# FDC.net
KiCad netlist of a schematic drawn in Altium Designer
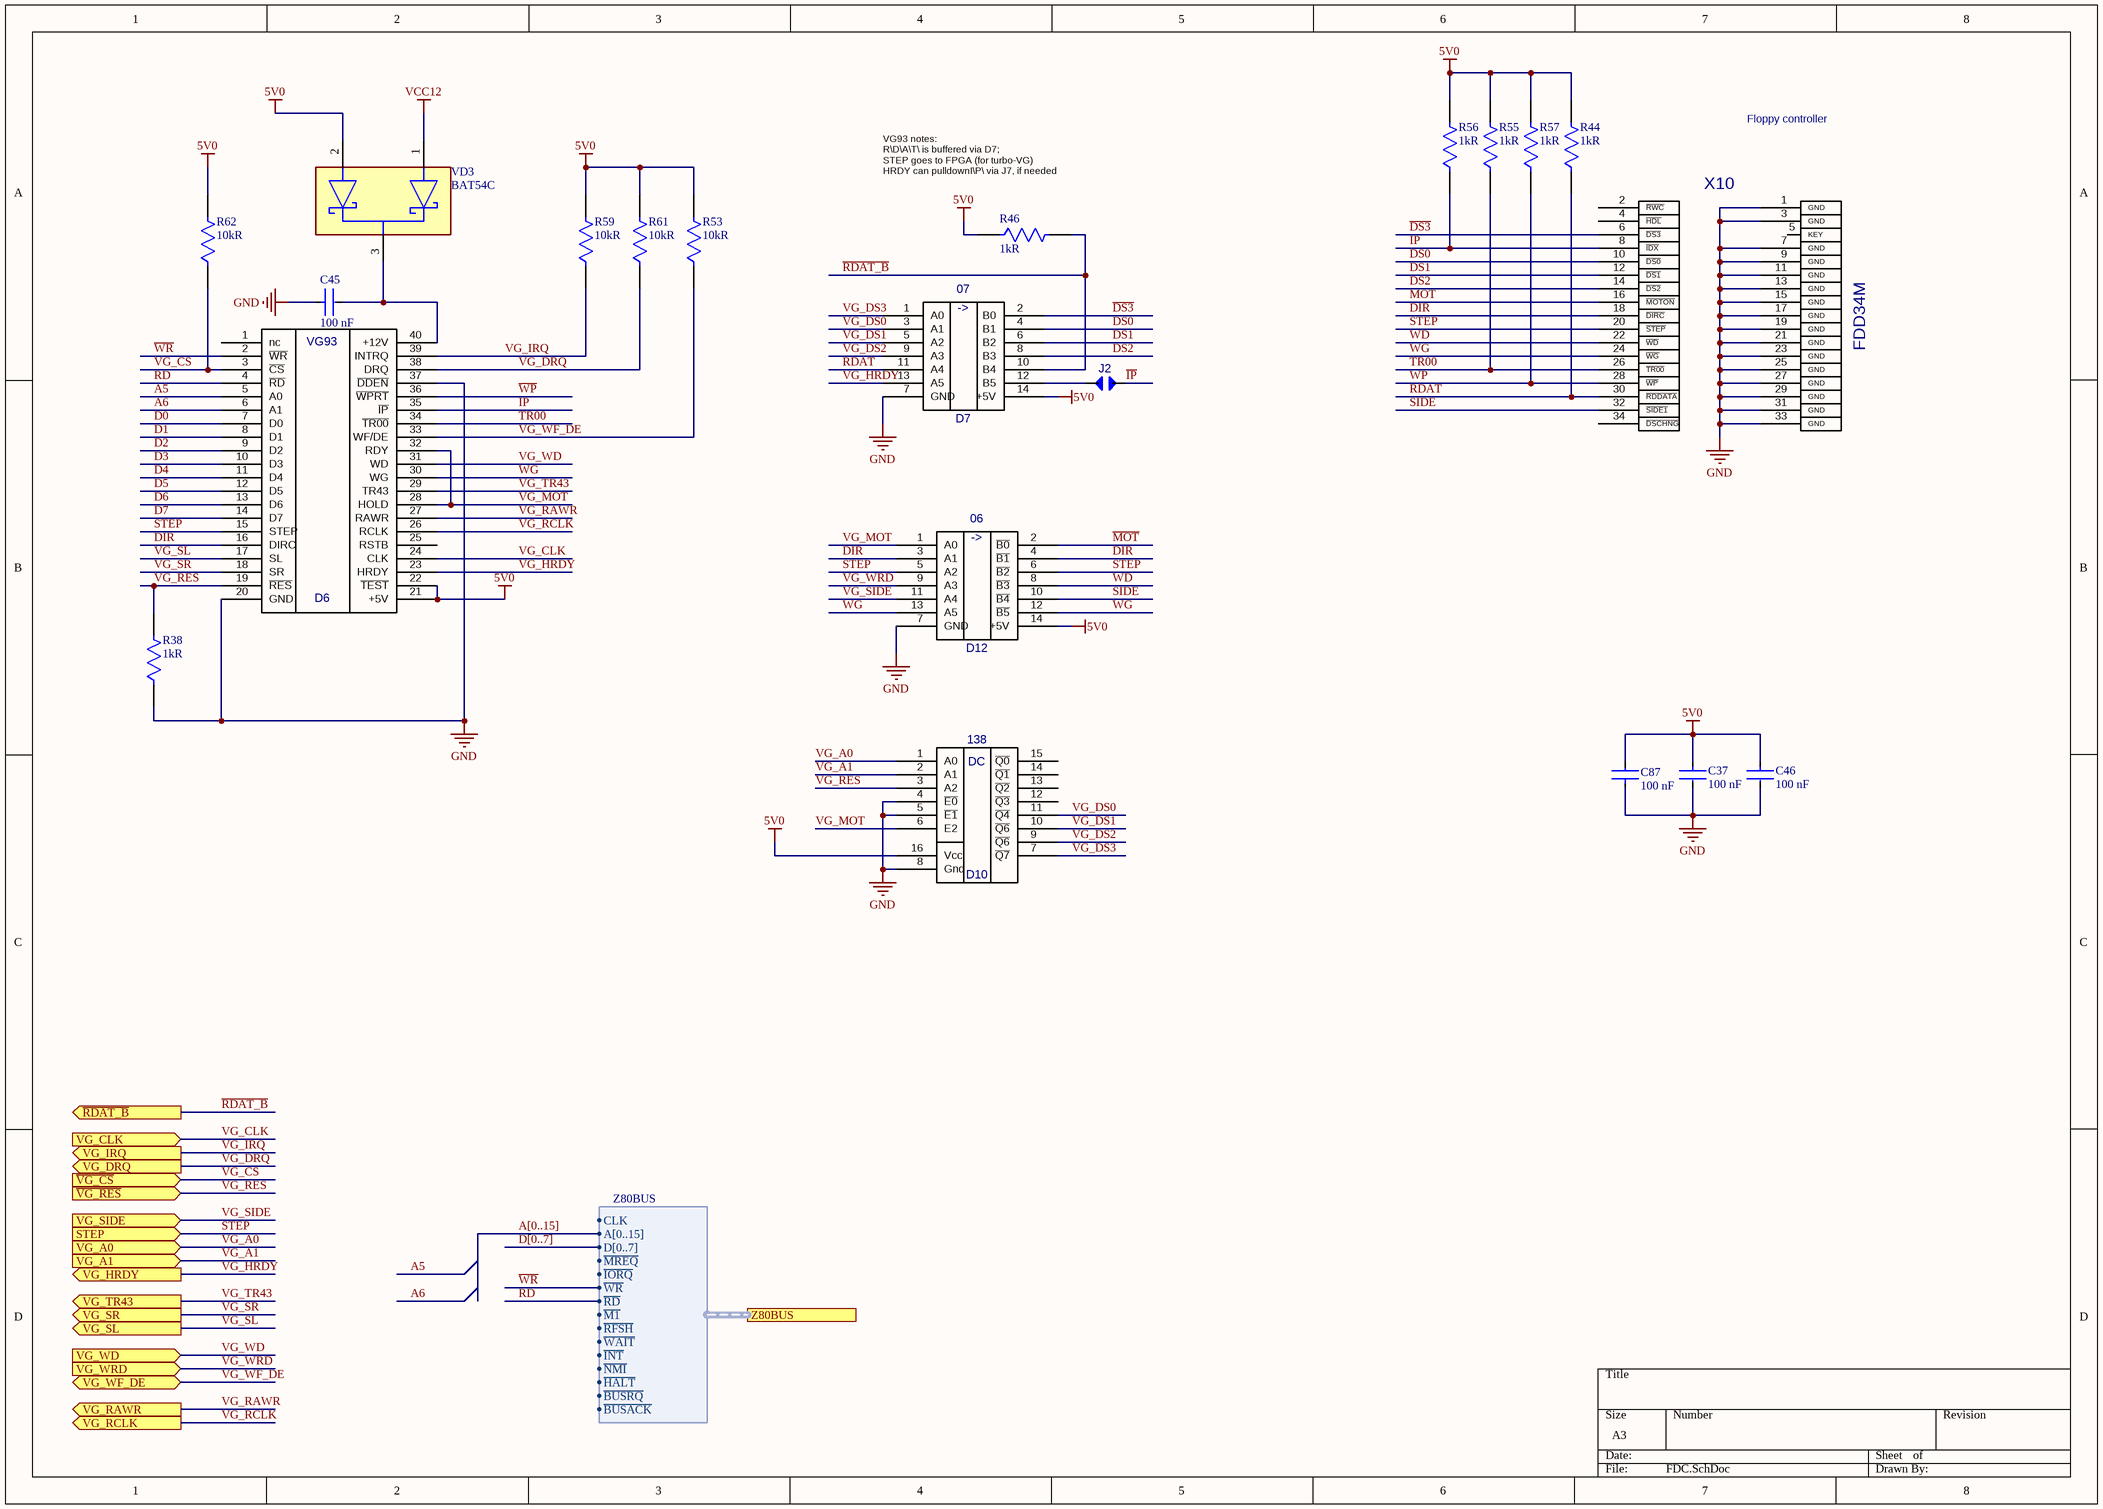
[diagram p0: FDC.SchDoc]

(export (version "E")
  (design (tool "Eeschema 10.0.6"))
  (components
    (comp (ref "C37")
      (value "CC0805KRX7R9BB104")
      (footprint "FP-CC0805-0_85-IPC_A")
      (description "CAP CER 0.1UF 50V X7R 0805")
      (fields (field (name "CAPACITANCE") "100 nF") (field (name "MANUFACTURER") "Yageo"))
      (libsource (lib "SchLib") (part "CMP-2100-03606-3"))
    )
    (comp (ref "C45")
      (value "CC0805KRX7R9BB104")
      (footprint "FP-CC0805-0_85-IPC_A")
      (description "CAP CER 0.1UF 50V X7R 0805")
      (fields (field (name "CAPACITANCE") "100 nF") (field (name "MANUFACTURER") "Yageo"))
      (libsource (lib "SchLib") (part "CMP-2100-03606-3"))
    )
    (comp (ref "C46")
      (value "CC0805KRX7R9BB104")
      (footprint "FP-CC0805-0_85-IPC_A")
      (description "CAP CER 0.1UF 50V X7R 0805")
      (fields (field (name "CAPACITANCE") "100 nF") (field (name "MANUFACTURER") "Yageo"))
      (libsource (lib "SchLib") (part "CMP-2100-03606-3"))
    )
    (comp (ref "C87")
      (value "CC0805KRX7R9BB104")
      (footprint "FP-CC0805-0_85-IPC_A")
      (description "CAP CER 0.1UF 50V X7R 0805")
      (fields (field (name "CAPACITANCE") "100 nF") (field (name "MANUFACTURER") "Yageo"))
      (libsource (lib "SchLib") (part "CMP-2100-03606-3"))
    )
    (comp (ref "D6") (value "KR1818VG93") (footprint "DIP40") (libsource (lib "SchLib") (part "KR1818VG93")))
    (comp (ref "D7") (value "07") (footprint "SO14") (libsource (lib "SchLib") (part "07")))
    (comp (ref "D10") (value "138") (footprint "SO16") (libsource (lib "SchLib") (part "138")))
    (comp (ref "D12") (value "06") (footprint "SO14") (libsource (lib "SchLib") (part "06")))
    (comp (ref "J2")
      (value "JUMPER")
      (footprint "JUMPER_JUMPER(Primary)")
      (description "HLT->~IP")
      (libsource (lib "SchLib") (part "JUMPER"))
    )
    (comp (ref "R38")
      (value "CRCW08051K00FKEAHP")
      (footprint "FP-CRCW0805-HPe3-IPC_A")
      (description "RES Thick Film, 1kΩ, 1%, 0.5W, 100ppm/°C, 0805")
      (fields (field (name "RESISTANCE") "1kR") (field (name "MANUFACTURER") "Vishay Dale"))
      (libsource (lib "SchLib") (part "CMP-02407-004529-1"))
    )
    (comp (ref "R44")
      (value "CRCW08051K00FKEAHP")
      (footprint "FP-CRCW0805-HPe3-IPC_A")
      (description "RES Thick Film, 1kΩ, 1%, 0.5W, 100ppm/°C, 0805")
      (fields (field (name "RESISTANCE") "1kR") (field (name "MANUFACTURER") "Vishay Dale"))
      (libsource (lib "SchLib") (part "CMP-02407-004529-1"))
    )
    (comp (ref "R46")
      (value "CRCW08051K00FKEAHP")
      (footprint "FP-CRCW0805-HPe3-IPC_A")
      (description "RES Thick Film, 1kΩ, 1%, 0.5W, 100ppm/°C, 0805")
      (fields (field (name "RESISTANCE") "1kR") (field (name "MANUFACTURER") "Vishay Dale"))
      (libsource (lib "SchLib") (part "CMP-02407-004529-1"))
    )
    (comp (ref "R53")
      (value "CR0805-JW-103ELF")
      (footprint "FP-CR0805-IPC_A")
      (description "Thick Film Chip Resistors 0805 10kΩ 0.125W 5% 200ppm/°C")
      (fields (field (name "RESISTANCE") "10kR") (field (name "MANUFACTURER") "Bourns"))
      (libsource (lib "SchLib") (part "CMP-07231-003873-1"))
    )
    (comp (ref "R55")
      (value "CRCW08051K00FKEAHP")
      (footprint "FP-CRCW0805-HPe3-IPC_A")
      (description "RES Thick Film, 1kΩ, 1%, 0.5W, 100ppm/°C, 0805")
      (fields (field (name "RESISTANCE") "1kR") (field (name "MANUFACTURER") "Vishay Dale"))
      (libsource (lib "SchLib") (part "CMP-02407-004529-1"))
    )
    (comp (ref "R56")
      (value "CRCW08051K00FKEAHP")
      (footprint "FP-CRCW0805-HPe3-IPC_A")
      (description "RES Thick Film, 1kΩ, 1%, 0.5W, 100ppm/°C, 0805")
      (fields (field (name "RESISTANCE") "1kR") (field (name "MANUFACTURER") "Vishay Dale"))
      (libsource (lib "SchLib") (part "CMP-02407-004529-1"))
    )
    (comp (ref "R57")
      (value "CRCW08051K00FKEAHP")
      (footprint "FP-CRCW0805-HPe3-IPC_A")
      (description "RES Thick Film, 1kΩ, 1%, 0.5W, 100ppm/°C, 0805")
      (fields (field (name "RESISTANCE") "1kR") (field (name "MANUFACTURER") "Vishay Dale"))
      (libsource (lib "SchLib") (part "CMP-02407-004529-1"))
    )
    (comp (ref "R59")
      (value "CR0805-JW-103ELF")
      (footprint "FP-CR0805-IPC_A")
      (description "Thick Film Chip Resistors 0805 10kΩ 0.125W 5% 200ppm/°C")
      (fields (field (name "RESISTANCE") "10kR") (field (name "MANUFACTURER") "Bourns"))
      (libsource (lib "SchLib") (part "CMP-07231-003873-1"))
    )
    (comp (ref "R61")
      (value "CR0805-JW-103ELF")
      (footprint "FP-CR0805-IPC_A")
      (description "Thick Film Chip Resistors 0805 10kΩ 0.125W 5% 200ppm/°C")
      (fields (field (name "RESISTANCE") "10kR") (field (name "MANUFACTURER") "Bourns"))
      (libsource (lib "SchLib") (part "CMP-07231-003873-1"))
    )
    (comp (ref "R62")
      (value "CR0805-JW-103ELF")
      (footprint "FP-CR0805-IPC_A")
      (description "Thick Film Chip Resistors 0805 10kΩ 0.125W 5% 200ppm/°C")
      (fields (field (name "RESISTANCE") "10kR") (field (name "MANUFACTURER") "Bourns"))
      (libsource (lib "SchLib") (part "CMP-07231-003873-1"))
    )
    (comp (ref "VD3")
      (value "BAT54C")
      (footprint "FP-MA03D-MFG")
      (description "DIODE ARRAY SCHOTTKY 30V SOT23-3")
      (fields (field (name "MANUFACTURER") "ON Semiconductor / Fairchild"))
      (libsource (lib "SchLib") (part "CMP-07162-000010-1"))
    )
    (comp (ref "X10") (value "FDD34M") (footprint "FDD34M") (libsource (lib "SchLib") (part "FDD34M")))
  )
  (nets
    (net (code "16") (name "/A5") (class "Default")
      (node (ref "D6") (pin "5") (pinfunction "A0_5") (pintype "passive"))
    )
    (net (code "17") (name "/A6") (class "Default")
      (node (ref "D6") (pin "6") (pinfunction "A1_6") (pintype "passive"))
    )
    (net (code "19") (name "/D0") (class "Default")
      (node (ref "D6") (pin "7") (pinfunction "D0_7") (pintype "passive"))
    )
    (net (code "20") (name "/D1") (class "Default")
      (node (ref "D6") (pin "8") (pinfunction "D1_8") (pintype "passive"))
    )
    (net (code "21") (name "/D2") (class "Default")
      (node (ref "D6") (pin "9") (pinfunction "D2_9") (pintype "passive"))
    )
    (net (code "22") (name "/D3") (class "Default")
      (node (ref "D6") (pin "10") (pinfunction "D3_10") (pintype "passive"))
    )
    (net (code "23") (name "/D4") (class "Default")
      (node (ref "D6") (pin "11") (pinfunction "D4_11") (pintype "passive"))
    )
    (net (code "24") (name "/D5") (class "Default")
      (node (ref "D6") (pin "12") (pinfunction "D5_12") (pintype "passive"))
    )
    (net (code "25") (name "/D6") (class "Default")
      (node (ref "D6") (pin "13") (pinfunction "D6_13") (pintype "passive"))
    )
    (net (code "26") (name "/D7") (class "Default")
      (node (ref "D6") (pin "14") (pinfunction "D7_14") (pintype "passive"))
    )
    (net (code "27") (name "/DIR") (class "Default")
      (node (ref "D12") (pin "3") (pinfunction "A1_3") (pintype "passive"))
      (node (ref "D6") (pin "16") (pinfunction "DIRC_16") (pintype "passive"))
    )
    (net (code "29") (name "/STEP") (class "Default")
      (node (ref "D12") (pin "5") (pinfunction "A2_5") (pintype "passive"))
      (node (ref "D6") (pin "15") (pinfunction "STEP_15") (pintype "passive"))
    )
    (net (code "30") (name "/VG_A0") (class "Default")
      (node (ref "D10") (pin "1") (pinfunction "A0_1") (pintype "passive"))
    )
    (net (code "31") (name "/VG_A1") (class "Default")
      (node (ref "D10") (pin "2") (pinfunction "A1_2") (pintype "passive"))
    )
    (net (code "32") (name "/VG_CLK") (class "Default")
      (node (ref "D6") (pin "24") (pinfunction "CLK_24") (pintype "passive"))
    )
    (net (code "33") (name "/VG_DRQ") (class "Default")
      (node (ref "D6") (pin "38") (pinfunction "DRQ_38") (pintype "passive"))
      (node (ref "R61") (pin "1") (pinfunction "1_1") (pintype "passive"))
    )
    (net (code "34") (name "/VG_DS0") (class "Default")
      (node (ref "D10") (pin "11") (pinfunction "~{Q4}_11") (pintype "passive"))
      (node (ref "D7") (pin "3") (pinfunction "A1_3") (pintype "passive"))
    )
    (net (code "35") (name "/VG_DS1") (class "Default")
      (node (ref "D10") (pin "10") (pinfunction "~{Q6}_10") (pintype "passive"))
      (node (ref "D7") (pin "5") (pinfunction "A2_5") (pintype "passive"))
    )
    (net (code "36") (name "/VG_DS2") (class "Default")
      (node (ref "D10") (pin "9") (pinfunction "~{Q6}_9") (pintype "passive"))
      (node (ref "D7") (pin "9") (pinfunction "A3_9") (pintype "passive"))
    )
    (net (code "37") (name "/VG_DS3") (class "Default")
      (node (ref "D10") (pin "7") (pinfunction "~{Q7}_7") (pintype "passive"))
      (node (ref "D7") (pin "1") (pinfunction "A0_1") (pintype "passive"))
    )
    (net (code "38") (name "/VG_HRDY") (class "Default")
      (node (ref "D6") (pin "23") (pinfunction "HRDY_23") (pintype "passive"))
      (node (ref "D7") (pin "13") (pinfunction "A5_13") (pintype "passive"))
    )
    (net (code "39") (name "/VG_IRQ") (class "Default")
      (node (ref "D6") (pin "39") (pinfunction "INTRQ_39") (pintype "passive"))
      (node (ref "R59") (pin "1") (pinfunction "1_1") (pintype "passive"))
    )
    (net (code "40") (name "/VG_MOT") (class "Default")
      (node (ref "D10") (pin "6") (pinfunction "E2_6") (pintype "passive"))
      (node (ref "D12") (pin "1") (pinfunction "A0_1") (pintype "passive"))
      (node (ref "D6") (pin "28") (pinfunction "HOLD_28") (pintype "passive"))
      (node (ref "D6") (pin "32") (pinfunction "RDY_32") (pintype "passive"))
    )
    (net (code "41") (name "/VG_RAWR") (class "Default")
      (node (ref "D6") (pin "27") (pinfunction "RAWR_27") (pintype "passive"))
    )
    (net (code "42") (name "/VG_RCLK") (class "Default")
      (node (ref "D6") (pin "26") (pinfunction "RCLK_26") (pintype "passive"))
    )
    (net (code "43") (name "/VG_SIDE") (class "Default")
      (node (ref "D12") (pin "11") (pinfunction "A4_11") (pintype "passive"))
    )
    (net (code "44") (name "/VG_SL") (class "Default")
      (node (ref "D6") (pin "17") (pinfunction "SL_17") (pintype "passive"))
    )
    (net (code "45") (name "/VG_SR") (class "Default")
      (node (ref "D6") (pin "18") (pinfunction "SR_18") (pintype "passive"))
    )
    (net (code "46") (name "/VG_TR43") (class "Default")
      (node (ref "D6") (pin "29") (pinfunction "TR43_29") (pintype "passive"))
    )
    (net (code "47") (name "/VG_WD") (class "Default")
      (node (ref "D6") (pin "31") (pinfunction "WD_31") (pintype "passive"))
    )
    (net (code "48") (name "/VG_WF_DE") (class "Default")
      (node (ref "D6") (pin "33") (pinfunction "WF/DE_33") (pintype "passive"))
      (node (ref "R53") (pin "1") (pinfunction "1_1") (pintype "passive"))
    )
    (net (code "49") (name "/VG_WRD") (class "Default")
      (node (ref "D12") (pin "9") (pinfunction "A3_9") (pintype "passive"))
    )
    (net (code "50") (name "/WG") (class "Default")
      (node (ref "D12") (pin "13") (pinfunction "A5_13") (pintype "passive"))
      (node (ref "D6") (pin "30") (pinfunction "WG_30") (pintype "passive"))
    )
    (net (code "52") (name "/~{DIR}") (class "Default")
      (node (ref "D12") (pin "4") (pinfunction "~{B1}_4") (pintype "passive"))
      (node (ref "X10") (pin "18") (pinfunction "~{DIRC}_18") (pintype "passive"))
    )
    (net (code "53") (name "/~{DS0}") (class "Default")
      (node (ref "D7") (pin "4") (pinfunction "B1_4") (pintype "passive"))
      (node (ref "X10") (pin "10") (pinfunction "~{DS0}_10") (pintype "passive"))
    )
    (net (code "54") (name "/~{DS1}") (class "Default")
      (node (ref "D7") (pin "6") (pinfunction "B2_6") (pintype "passive"))
      (node (ref "X10") (pin "12") (pinfunction "~{DS1}_12") (pintype "passive"))
    )
    (net (code "55") (name "/~{DS2}") (class "Default")
      (node (ref "D7") (pin "8") (pinfunction "B3_8") (pintype "passive"))
      (node (ref "X10") (pin "14") (pinfunction "~{DS2}_14") (pintype "passive"))
    )
    (net (code "56") (name "/~{DS3}") (class "Default")
      (node (ref "D7") (pin "2") (pinfunction "B0_2") (pintype "passive"))
      (node (ref "X10") (pin "6") (pinfunction "~{DS3}_6") (pintype "passive"))
    )
    (net (code "57") (name "/~{IP}") (class "Default")
      (node (ref "D6") (pin "35") (pinfunction "~{IP}_35") (pintype "passive"))
      (node (ref "J2") (pin "1") (pinfunction "2_1") (pintype "passive"))
      (node (ref "R56") (pin "1") (pinfunction "1_1") (pintype "passive"))
      (node (ref "X10") (pin "8") (pinfunction "~{IDX}_8") (pintype "passive"))
    )
    (net (code "58") (name "/~{MOT}") (class "Default")
      (node (ref "D12") (pin "2") (pinfunction "~{B0}_2") (pintype "passive"))
      (node (ref "X10") (pin "16") (pinfunction "~{MOTON}_16") (pintype "passive"))
    )
    (net (code "59") (name "/~{RDAT_B}") (class "Default")
      (node (ref "D7") (pin "10") (pinfunction "B4_10") (pintype "passive"))
      (node (ref "R46") (pin "2") (pinfunction "2_2") (pintype "passive"))
    )
    (net (code "60") (name "/~{RDAT}") (class "Default")
      (node (ref "D7") (pin "11") (pinfunction "A4_11") (pintype "passive"))
      (node (ref "R44") (pin "1") (pinfunction "1_1") (pintype "passive"))
      (node (ref "X10") (pin "30") (pinfunction "~{RDDATA}_30") (pintype "passive"))
    )
    (net (code "61") (name "/~{RD}") (class "Default")
      (node (ref "D6") (pin "4") (pinfunction "~{RD}_4") (pintype "passive"))
    )
    (net (code "62") (name "/~{SIDE}") (class "Default")
      (node (ref "D12") (pin "10") (pinfunction "~{B4}_10") (pintype "passive"))
      (node (ref "X10") (pin "32") (pinfunction "~{SIDE1}_32") (pintype "passive"))
    )
    (net (code "63") (name "/~{STEP}") (class "Default")
      (node (ref "D12") (pin "6") (pinfunction "~{B2}_6") (pintype "passive"))
      (node (ref "X10") (pin "20") (pinfunction "~{STEP}_20") (pintype "passive"))
    )
    (net (code "64") (name "/~{TR00}") (class "Default")
      (node (ref "D6") (pin "34") (pinfunction "~{TR00}_34") (pintype "passive"))
      (node (ref "R55") (pin "1") (pinfunction "1_1") (pintype "passive"))
      (node (ref "X10") (pin "26") (pinfunction "~{TR00}_26") (pintype "passive"))
    )
    (net (code "65") (name "/~{VG_CS}") (class "Default")
      (node (ref "D6") (pin "3") (pinfunction "~{CS}_3") (pintype "passive"))
      (node (ref "R62") (pin "1") (pinfunction "1_1") (pintype "passive"))
    )
    (net (code "66") (name "/~{VG_RES}") (class "Default")
      (node (ref "D10") (pin "3") (pinfunction "A2_3") (pintype "passive"))
      (node (ref "D6") (pin "19") (pinfunction "~{RES}_19") (pintype "passive"))
      (node (ref "R38") (pin "2") (pinfunction "2_2") (pintype "passive"))
    )
    (net (code "67") (name "/~{WD}") (class "Default")
      (node (ref "D12") (pin "8") (pinfunction "~{B3}_8") (pintype "passive"))
      (node (ref "X10") (pin "22") (pinfunction "~{WD}_22") (pintype "passive"))
    )
    (net (code "68") (name "/~{WG}") (class "Default")
      (node (ref "D12") (pin "12") (pinfunction "~{B5}_12") (pintype "passive"))
      (node (ref "X10") (pin "24") (pinfunction "~{WG}_24") (pintype "passive"))
    )
    (net (code "69") (name "/~{WP}") (class "Default")
      (node (ref "D6") (pin "36") (pinfunction "~{WPRT}_36") (pintype "passive"))
      (node (ref "R57") (pin "1") (pinfunction "1_1") (pintype "passive"))
      (node (ref "X10") (pin "28") (pinfunction "~{WP}_28") (pintype "passive"))
    )
    (net (code "70") (name "/~{WR}") (class "Default")
      (node (ref "D6") (pin "2") (pinfunction "~{WR}_2") (pintype "passive"))
    )
    (net (code "71") (name "5V0") (class "Default")
      (node (ref "C37") (pin "1") (pinfunction "1_1") (pintype "passive"))
      (node (ref "C46") (pin "1") (pinfunction "1_1") (pintype "passive"))
      (node (ref "C87") (pin "2") (pinfunction "2_2") (pintype "passive"))
      (node (ref "D10") (pin "16") (pinfunction "Vcc_16") (pintype "passive"))
      (node (ref "D12") (pin "14") (pinfunction "+5V_14") (pintype "passive"))
      (node (ref "D6") (pin "21") (pinfunction "+5V_21") (pintype "passive"))
      (node (ref "D6") (pin "22") (pinfunction "~{TEST}_22") (pintype "passive"))
      (node (ref "D7") (pin "14") (pinfunction "+5V_14") (pintype "passive"))
      (node (ref "R44") (pin "2") (pinfunction "2_2") (pintype "passive"))
      (node (ref "R46") (pin "1") (pinfunction "1_1") (pintype "passive"))
      (node (ref "R53") (pin "2") (pinfunction "2_2") (pintype "passive"))
      (node (ref "R55") (pin "2") (pinfunction "2_2") (pintype "passive"))
      (node (ref "R56") (pin "2") (pinfunction "2_2") (pintype "passive"))
      (node (ref "R57") (pin "2") (pinfunction "2_2") (pintype "passive"))
      (node (ref "R59") (pin "2") (pinfunction "2_2") (pintype "passive"))
      (node (ref "R61") (pin "2") (pinfunction "2_2") (pintype "passive"))
      (node (ref "R62") (pin "2") (pinfunction "2_2") (pintype "passive"))
      (node (ref "VD3") (pin "2") (pinfunction "2_ANODE_2") (pintype "passive"))
    )
    (net (code "72") (name "GND") (class "Default")
      (node (ref "C37") (pin "2") (pinfunction "2_2") (pintype "passive"))
      (node (ref "C45") (pin "1") (pinfunction "1_1") (pintype "passive"))
      (node (ref "C46") (pin "2") (pinfunction "2_2") (pintype "passive"))
      (node (ref "C87") (pin "1") (pinfunction "1_1") (pintype "passive"))
      (node (ref "D10") (pin "4") (pinfunction "~{E0}_4") (pintype "passive"))
      (node (ref "D10") (pin "5") (pinfunction "~{E1}_5") (pintype "passive"))
      (node (ref "D10") (pin "8") (pinfunction "Gnd_8") (pintype "passive"))
      (node (ref "D12") (pin "7") (pinfunction "GND_7") (pintype "passive"))
      (node (ref "D6") (pin "20") (pinfunction "GND_20") (pintype "passive"))
      (node (ref "D6") (pin "37") (pinfunction "~{DDEN}_37") (pintype "passive"))
      (node (ref "D7") (pin "7") (pinfunction "GND_7") (pintype "passive"))
      (node (ref "R38") (pin "1") (pinfunction "1_1") (pintype "passive"))
      (node (ref "X10") (pin "1") (pinfunction "GND_1") (pintype "passive"))
      (node (ref "X10") (pin "11") (pinfunction "GND_11") (pintype "passive"))
      (node (ref "X10") (pin "13") (pinfunction "GND_13") (pintype "passive"))
      (node (ref "X10") (pin "15") (pinfunction "GND_15") (pintype "passive"))
      (node (ref "X10") (pin "17") (pinfunction "GND_17") (pintype "passive"))
      (node (ref "X10") (pin "19") (pinfunction "GND_19") (pintype "passive"))
      (node (ref "X10") (pin "21") (pinfunction "GND_21") (pintype "passive"))
      (node (ref "X10") (pin "23") (pinfunction "GND_23") (pintype "passive"))
      (node (ref "X10") (pin "25") (pinfunction "GND_25") (pintype "passive"))
      (node (ref "X10") (pin "27") (pinfunction "GND_27") (pintype "passive"))
      (node (ref "X10") (pin "29") (pinfunction "GND_29") (pintype "passive"))
      (node (ref "X10") (pin "3") (pinfunction "GND_3") (pintype "passive"))
      (node (ref "X10") (pin "31") (pinfunction "GND_31") (pintype "passive"))
      (node (ref "X10") (pin "33") (pinfunction "GND_33") (pintype "passive"))
      (node (ref "X10") (pin "7") (pinfunction "GND_7") (pintype "passive"))
      (node (ref "X10") (pin "9") (pinfunction "GND_9") (pintype "passive"))
    )
    (net (code "73") (name "Net-(D6-+12V)") (class "Default")
      (node (ref "C45") (pin "2") (pinfunction "2_2") (pintype "passive"))
      (node (ref "D6") (pin "40") (pinfunction "+12V_40") (pintype "passive"))
      (node (ref "VD3") (pin "3") (pinfunction "COMMON_CATHODE_3") (pintype "passive"))
    )
    (net (code "74") (name "Net-(D7-B5)") (class "Default")
      (node (ref "D7") (pin "12") (pinfunction "B5_12") (pintype "passive"))
      (node (ref "J2") (pin "0") (pinfunction "1_0") (pintype "passive"))
    )
    (net (code "75") (name "VCC12") (class "Default")
      (node (ref "VD3") (pin "1") (pinfunction "1_ANODE_1") (pintype "passive"))
    )
    (net (code "76") (name "unconnected-(D6-RSTB-Pad25)") (class "Default")
      (node (ref "D6") (pin "25") (pinfunction "RSTB_25") (pintype "passive"))
    )
    (net (code "77") (name "unconnected-(D6-nc-Pad1)") (class "Default")
      (node (ref "D6") (pin "1") (pinfunction "nc_1") (pintype "passive"))
    )
    (net (code "78") (name "unconnected-(D10-~{Q0}-Pad15)") (class "Default")
      (node (ref "D10") (pin "15") (pinfunction "~{Q0}_15") (pintype "passive"))
    )
    (net (code "79") (name "unconnected-(D10-~{Q1}-Pad14)") (class "Default")
      (node (ref "D10") (pin "14") (pinfunction "~{Q1}_14") (pintype "passive"))
    )
    (net (code "80") (name "unconnected-(D10-~{Q2}-Pad13)") (class "Default")
      (node (ref "D10") (pin "13") (pinfunction "~{Q2}_13") (pintype "passive"))
    )
    (net (code "81") (name "unconnected-(D10-~{Q3}-Pad12)") (class "Default")
      (node (ref "D10") (pin "12") (pinfunction "~{Q3}_12") (pintype "passive"))
    )
    (net (code "82") (name "unconnected-(X10-KEY-Pad5)") (class "Default")
      (node (ref "X10") (pin "5") (pinfunction "KEY_5") (pintype "passive"))
    )
    (net (code "83") (name "unconnected-(X10-~{DSCHNG}-Pad34)") (class "Default")
      (node (ref "X10") (pin "34") (pinfunction "~{DSCHNG}_34") (pintype "passive"))
    )
    (net (code "84") (name "unconnected-(X10-~{HDL}-Pad4)") (class "Default")
      (node (ref "X10") (pin "4") (pinfunction "~{HDL}_4") (pintype "passive"))
    )
    (net (code "85") (name "unconnected-(X10-~{RWC}-Pad2)") (class "Default")
      (node (ref "X10") (pin "2") (pinfunction "~{RWC}_2") (pintype "passive"))
    )
  )
)
